# MINI_SAM_2017-01-012.net
KiCad netlist of a schematic drawn in EAGLE
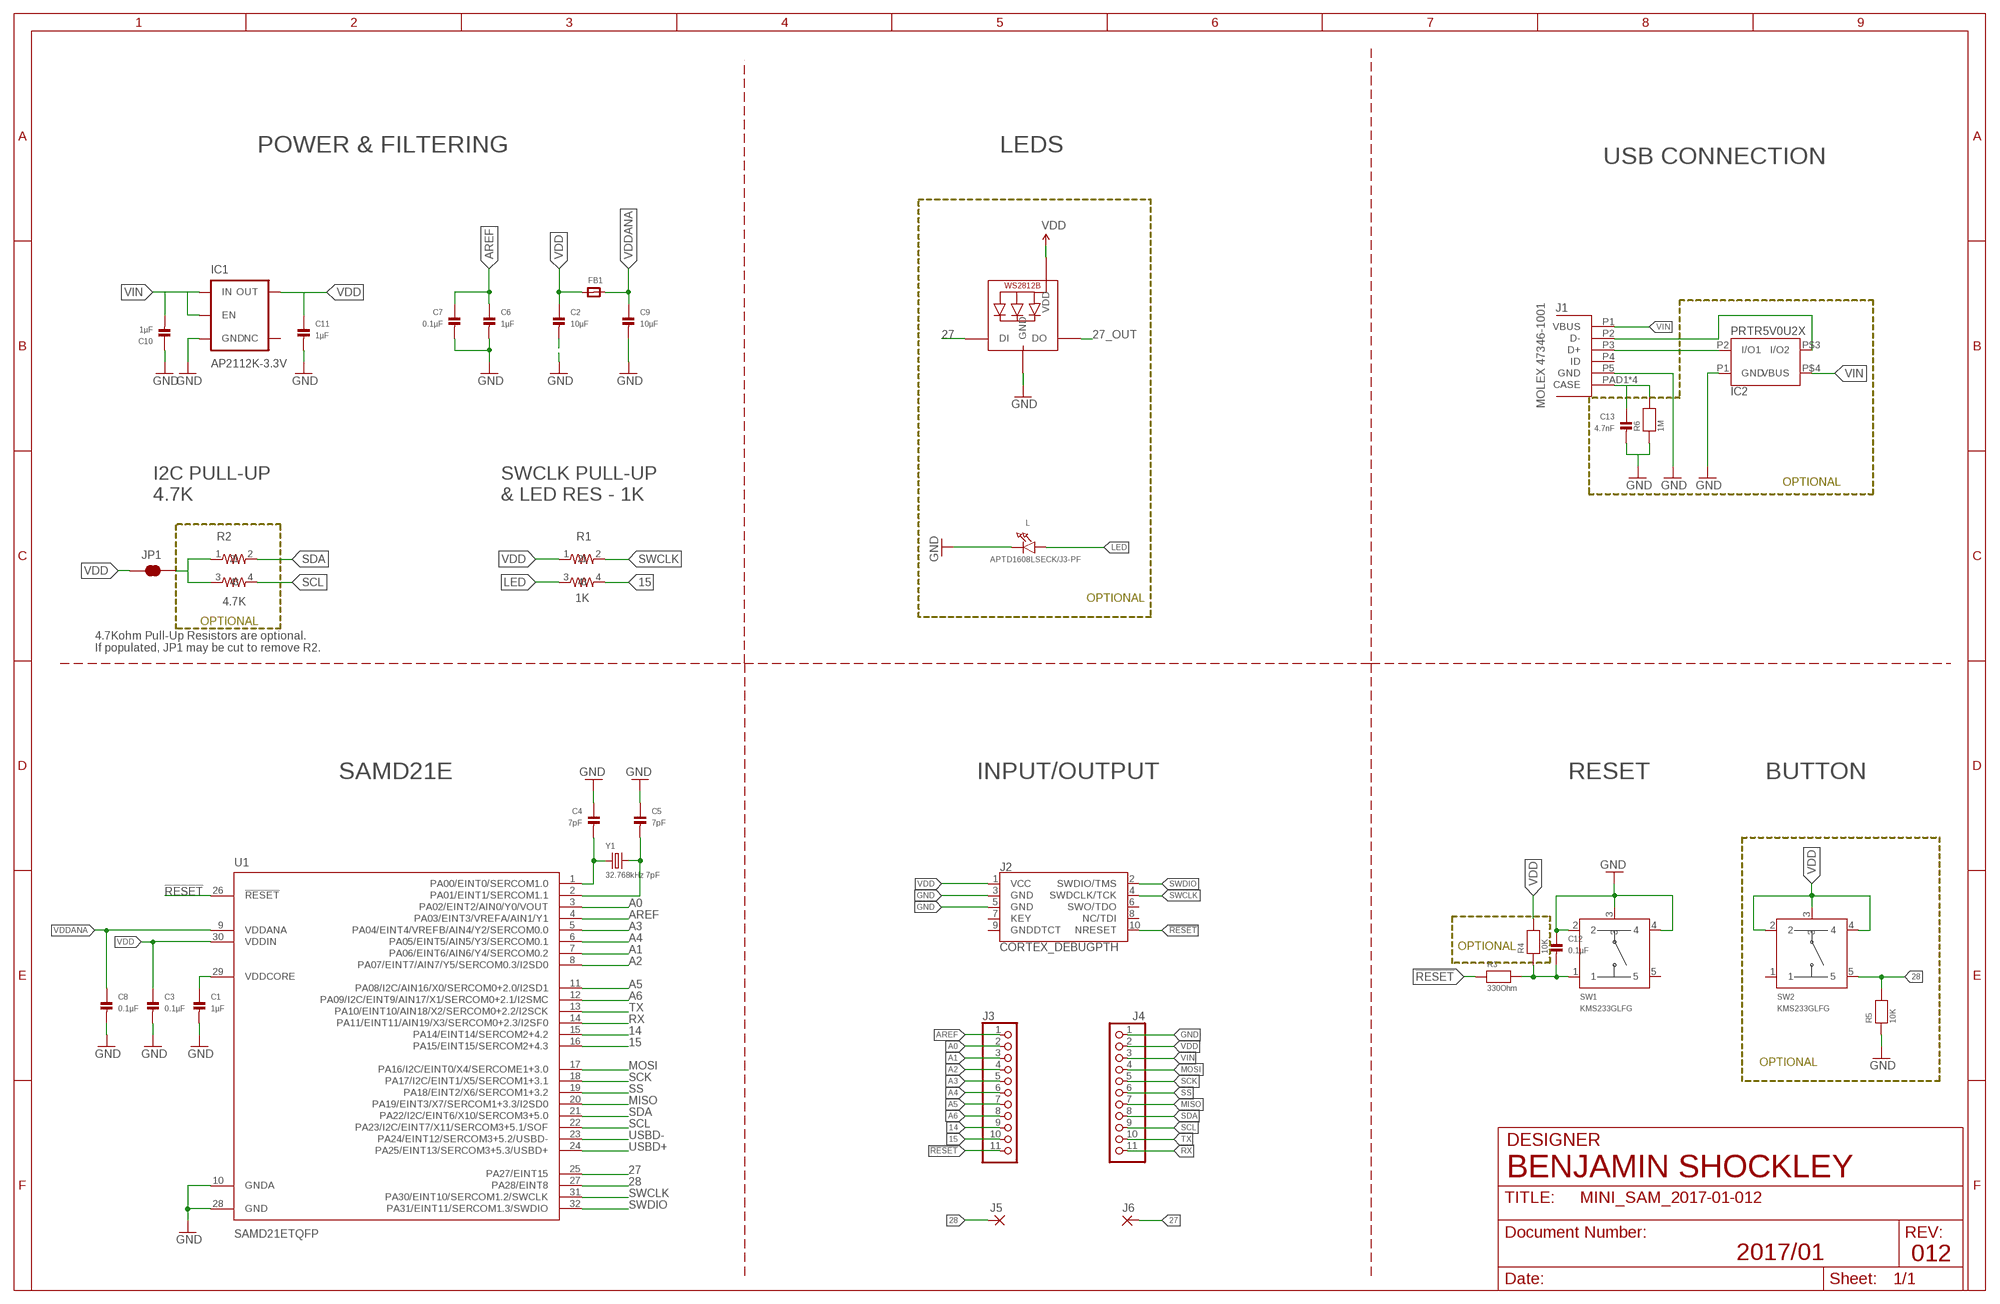
[diagram p0: schematic, sheet 1]

(export (version "E")
  (design (tool "Eeschema 10.0.6"))
  (components
    (comp (ref "C1")
      (value "1µF")
      (footprint "eagle-import:_0805MP")
      (libsource (lib "eagle-import") (part "CAP_CERAMIC_0805MP"))
    )
    (comp (ref "C2")
      (value "10µF")
      (footprint "eagle-import:_0805MP")
      (libsource (lib "eagle-import") (part "CAP_CERAMIC_0805MP"))
    )
    (comp (ref "C3")
      (value "0.1µF")
      (footprint "eagle-import:_0805MP")
      (libsource (lib "eagle-import") (part "CAP_CERAMIC_0805MP"))
    )
    (comp (ref "C4")
      (value "7pF")
      (footprint "eagle-import:_0805MP")
      (libsource (lib "eagle-import") (part "CAP_CERAMIC_0805MP"))
    )
    (comp (ref "C5")
      (value "7pF")
      (footprint "eagle-import:_0805MP")
      (libsource (lib "eagle-import") (part "CAP_CERAMIC_0805MP"))
    )
    (comp (ref "C6")
      (value "1µF")
      (footprint "eagle-import:_0805MP")
      (libsource (lib "eagle-import") (part "CAP_CERAMIC_0805MP"))
    )
    (comp (ref "C7")
      (value "0.1µF")
      (footprint "eagle-import:_0805MP")
      (libsource (lib "eagle-import") (part "CAP_CERAMIC_0805MP"))
    )
    (comp (ref "C8")
      (value "0.1µF")
      (footprint "eagle-import:_0805MP")
      (libsource (lib "eagle-import") (part "CAP_CERAMIC_0805MP"))
    )
    (comp (ref "C9")
      (value "10µF")
      (footprint "eagle-import:_0805MP")
      (libsource (lib "eagle-import") (part "CAP_CERAMIC_0805MP"))
    )
    (comp (ref "C10")
      (value "1µF")
      (footprint "eagle-import:_0805MP")
      (libsource (lib "eagle-import") (part "CAP_CERAMIC_0805MP"))
    )
    (comp (ref "C11")
      (value "1µF")
      (footprint "eagle-import:_0805MP")
      (libsource (lib "eagle-import") (part "CAP_CERAMIC_0805MP"))
    )
    (comp (ref "C12")
      (value "0.1µF")
      (footprint "eagle-import:_0805MP")
      (libsource (lib "eagle-import") (part "CAP_CERAMIC_0805MP"))
    )
    (comp (ref "C13")
      (value "4.7nF")
      (footprint "eagle-import:_0805MP")
      (libsource (lib "eagle-import") (part "CAP_CERAMIC_0805MP"))
    )
    (comp (ref "FB1")
      (value "FERRITE_0805MP")
      (footprint "eagle-import:_0805MP")
      (libsource (lib "eagle-import") (part "FERRITE_0805MP"))
    )
    (comp (ref "IC1")
      (value "AP2112K-3.3V")
      (footprint "eagle-import:SOT23-5")
      (libsource (lib "eagle-import") (part "V_REG_AP2112K-3.3V"))
    )
    (comp (ref "IC2")
      (value "PRTR5V0U2X")
      (footprint "eagle-import:SOT143B_REFLOW")
      (libsource (lib "eagle-import") (part "PRTR5V0U2X"))
    )
    (comp (ref "J1")
      (value "MOLEX_47346-100147346")
      (footprint "eagle-import:MOLEX_47346-1001")
      (libsource (lib "eagle-import") (part "MOLEX_47346-100147346"))
    )
    (comp (ref "J2")
      (value "CORTEX_DEBUGPTH")
      (footprint "eagle-import:2X5-PTH-1.27MM")
      (libsource (lib "eagle-import") (part "CORTEX_DEBUGPTH"))
    )
    (comp (ref "J3")
      (value "PINHD-1X111X11_SMT")
      (footprint "eagle-import:1X11_SMT")
      (libsource (lib "eagle-import") (part "PINHD-1X111X11_SMT"))
    )
    (comp (ref "J4")
      (value "PINHD-1X111X11_SMT")
      (footprint "eagle-import:1X11_SMT")
      (libsource (lib "eagle-import") (part "PINHD-1X111X11_SMT"))
    )
    (comp (ref "J5")
      (value "FR11_PAD2MMX1MM")
      (footprint "eagle-import:SMD2MMX1MM")
      (libsource (lib "eagle-import") (part "FR11_PAD2MMX1MM"))
    )
    (comp (ref "J6")
      (value "FR11_PAD2MMX1MM")
      (footprint "eagle-import:SMD2MMX1MM")
      (libsource (lib "eagle-import") (part "FR11_PAD2MMX1MM"))
    )
    (comp (ref "JP1")
      (value "JUMPER-SMT_2_NC_TRACE_NO-SILK")
      (footprint "eagle-import:SMT-JUMPER_2_NC_TRACE_NO-SILK")
      (libsource (lib "eagle-import") (part "JUMPER-SMT_2_NC_TRACE_NO-SILK"))
    )
    (comp (ref "L")
      (value "APTD1608LSECK/J3-PF")
      (footprint "eagle-import:CHIPLED_0603_NOOUTLINE")
      (libsource (lib "eagle-import") (part "LED0603_NOOUTLINE"))
    )
    (comp (ref "R1")
      (value "1K")
      (footprint "eagle-import:RESISTOR_ARRAY_0606")
      (libsource (lib "eagle-import") (part "RESISTOR_ARRAY_2"))
    )
    (comp (ref "R2")
      (value "4.7K")
      (footprint "eagle-import:RESISTOR_ARRAY_0606")
      (libsource (lib "eagle-import") (part "RESISTOR_ARRAY_2"))
    )
    (comp (ref "R3")
      (value "330Ohm")
      (footprint "eagle-import:_0805MP")
      (libsource (lib "eagle-import") (part "RESISTOR_0805MP"))
    )
    (comp (ref "R4")
      (value "10K")
      (footprint "eagle-import:_0805MP")
      (libsource (lib "eagle-import") (part "RESISTOR_0805MP"))
    )
    (comp (ref "R5")
      (value "10K")
      (footprint "eagle-import:_0805MP")
      (libsource (lib "eagle-import") (part "RESISTOR_0805MP"))
    )
    (comp (ref "R6")
      (value "1M")
      (footprint "eagle-import:_0805MP")
      (libsource (lib "eagle-import") (part "RESISTOR_0805MP"))
    )
    (comp (ref "STATUS")
      (value "WS2812B3535")
      (footprint "eagle-import:LED3535")
      (libsource (lib "eagle-import") (part "WS2812B3535"))
    )
    (comp (ref "SW1")
      (value "KMS233GLFG")
      (footprint "eagle-import:KMS_SWITCH")
      (libsource (lib "eagle-import") (part "KMS_SWITCHKMS"))
    )
    (comp (ref "SW2")
      (value "KMS233GLFG")
      (footprint "eagle-import:KMS_SWITCH")
      (libsource (lib "eagle-import") (part "KMS_SWITCHKMS"))
    )
    (comp (ref "U1")
      (value "SAMD21ETQFP")
      (footprint "eagle-import:TQFP32-08")
      (libsource (lib "eagle-import") (part "SAMD21ETQFP"))
    )
    (comp (ref "Y1")
      (value "32.768kHz 7pF")
      (footprint "eagle-import:_0805MP")
      (libsource (lib "eagle-import") (part "CRYSTAL0805PACKAGE"))
    )
  )
  (nets
    (net (code "1") (name "/27_OUT") (class "Default")
      (node (ref "STATUS") (pin "3") (pinfunction "DO_3") (pintype "output"))
    )
    (net (code "2") (name "/USBD+") (class "Default")
      (node (ref "IC2") (pin "P2") (pinfunction "I/O1_P2") (pintype "bidirectional"))
      (node (ref "J1") (pin "P3") (pinfunction "D+_P3") (pintype "bidirectional"))
      (node (ref "U1") (pin "24") (pinfunction "PA25/EINT13/SERCOM3+5.3/USBD+_24") (pintype "bidirectional"))
    )
    (net (code "3") (name "/USBD-") (class "Default")
      (node (ref "IC2") (pin "P$3") (pinfunction "I/O2_P$3") (pintype "bidirectional"))
      (node (ref "J1") (pin "P2") (pinfunction "D-_P2") (pintype "bidirectional"))
      (node (ref "U1") (pin "23") (pinfunction "PA24/EINT12/SERCOM3+5.2/USBD-_23") (pintype "bidirectional"))
    )
    (net (code "4") (name "/~{RESET}") (class "Default")
      (node (ref "J2") (pin "10") (pinfunction "NRESET_10") (pintype "bidirectional"))
      (node (ref "J3") (pin "11") (pinfunction "11_11") (pintype "passive"))
      (node (ref "R3") (pin "1") (pinfunction "1_1") (pintype "passive"))
      (node (ref "U1") (pin "26") (pinfunction "~{RESET}_26") (pintype "bidirectional"))
    )
    (net (code "5") (name "14") (class "Default")
      (node (ref "J3") (pin "9") (pinfunction "9_9") (pintype "passive"))
      (node (ref "U1") (pin "15") (pinfunction "PA14/EINT14/SERCOM2+4.2_15") (pintype "bidirectional"))
    )
    (net (code "6") (name "15") (class "Default")
      (node (ref "J3") (pin "10") (pinfunction "10_10") (pintype "passive"))
      (node (ref "R1") (pin "4") (pinfunction "4_4") (pintype "passive"))
      (node (ref "U1") (pin "16") (pinfunction "PA15/EINT15/SERCOM2+4.3_16") (pintype "bidirectional"))
    )
    (net (code "7") (name "27") (class "Default")
      (node (ref "J6") (pin "P$1") (pinfunction "P_P$1") (pintype "passive"))
      (node (ref "STATUS") (pin "1") (pinfunction "DI_1") (pintype "input"))
      (node (ref "U1") (pin "25") (pinfunction "PA27/EINT15_25") (pintype "bidirectional"))
    )
    (net (code "8") (name "28") (class "Default")
      (node (ref "J5") (pin "P$1") (pinfunction "P_P$1") (pintype "passive"))
      (node (ref "R5") (pin "2") (pinfunction "2_2") (pintype "passive"))
      (node (ref "SW2") (pin "5") (pinfunction "5_5") (pintype "bidirectional"))
      (node (ref "U1") (pin "27") (pinfunction "PA28/EINT8_27") (pintype "bidirectional"))
    )
    (net (code "9") (name "A0") (class "Default")
      (node (ref "J3") (pin "2") (pinfunction "2_2") (pintype "passive"))
      (node (ref "U1") (pin "3") (pinfunction "PA02/EINT2/AIN0/Y0/VOUT_3") (pintype "bidirectional"))
    )
    (net (code "10") (name "A1") (class "Default")
      (node (ref "J3") (pin "3") (pinfunction "3_3") (pintype "passive"))
      (node (ref "U1") (pin "7") (pinfunction "PA06/EINT6/AIN6/Y4/SERCOM0.2_7") (pintype "bidirectional"))
    )
    (net (code "11") (name "A2") (class "Default")
      (node (ref "J3") (pin "4") (pinfunction "4_4") (pintype "passive"))
      (node (ref "U1") (pin "8") (pinfunction "PA07/EINT7/AIN7/Y5/SERCOM0.3/I2SD0_8") (pintype "bidirectional"))
    )
    (net (code "12") (name "A3") (class "Default")
      (node (ref "J3") (pin "5") (pinfunction "5_5") (pintype "passive"))
      (node (ref "U1") (pin "5") (pinfunction "PA04/EINT4/VREFB/AIN4/Y2/SERCOM0.0_5") (pintype "bidirectional"))
    )
    (net (code "13") (name "A4") (class "Default")
      (node (ref "J3") (pin "6") (pinfunction "6_6") (pintype "passive"))
      (node (ref "U1") (pin "6") (pinfunction "PA05/EINT5/AIN5/Y3/SERCOM0.1_6") (pintype "bidirectional"))
    )
    (net (code "14") (name "A5") (class "Default")
      (node (ref "J3") (pin "7") (pinfunction "7_7") (pintype "passive"))
      (node (ref "U1") (pin "11") (pinfunction "PA08/I2C/AIN16/X0/SERCOM0+2.0/I2SD1_11") (pintype "bidirectional"))
    )
    (net (code "15") (name "A6") (class "Default")
      (node (ref "J3") (pin "8") (pinfunction "8_8") (pintype "passive"))
      (node (ref "U1") (pin "12") (pinfunction "PA09/I2C/EINT9/AIN17/X1/SERCOM0+2.1/I2SMC_12") (pintype "bidirectional"))
    )
    (net (code "16") (name "AREF") (class "Default")
      (node (ref "C6") (pin "1") (pinfunction "P$1_1") (pintype "passive"))
      (node (ref "C7") (pin "1") (pinfunction "P$1_1") (pintype "passive"))
      (node (ref "J3") (pin "1") (pinfunction "1_1") (pintype "passive"))
      (node (ref "U1") (pin "4") (pinfunction "PA03/EINT3/VREFA/AIN1/Y1_4") (pintype "bidirectional"))
    )
    (net (code "17") (name "GND") (class "Default")
      (node (ref "C1") (pin "2") (pinfunction "P$2_2") (pintype "passive"))
      (node (ref "C10") (pin "1") (pinfunction "P$1_1") (pintype "passive"))
      (node (ref "C11") (pin "2") (pinfunction "P$2_2") (pintype "passive"))
      (node (ref "C12") (pin "1") (pinfunction "P$1_1") (pintype "passive"))
      (node (ref "C13") (pin "2") (pinfunction "P$2_2") (pintype "passive"))
      (node (ref "C2") (pin "2") (pinfunction "P$2_2") (pintype "passive"))
      (node (ref "C3") (pin "2") (pinfunction "P$2_2") (pintype "passive"))
      (node (ref "C4") (pin "1") (pinfunction "P$1_1") (pintype "passive"))
      (node (ref "C5") (pin "1") (pinfunction "P$1_1") (pintype "passive"))
      (node (ref "C6") (pin "2") (pinfunction "P$2_2") (pintype "passive"))
      (node (ref "C7") (pin "2") (pinfunction "P$2_2") (pintype "passive"))
      (node (ref "C8") (pin "2") (pinfunction "P$2_2") (pintype "passive"))
      (node (ref "C9") (pin "2") (pinfunction "P$2_2") (pintype "passive"))
      (node (ref "IC1") (pin "2") (pinfunction "GND_2") (pintype "input"))
      (node (ref "IC2") (pin "P1") (pinfunction "GND_P1") (pintype "bidirectional"))
      (node (ref "J1") (pin "P5") (pinfunction "GND_P5") (pintype "power_in"))
      (node (ref "J2") (pin "3") (pinfunction "GND_3") (pintype "bidirectional"))
      (node (ref "J2") (pin "5") (pinfunction "GND_5") (pintype "bidirectional"))
      (node (ref "J4") (pin "1") (pinfunction "1_1") (pintype "passive"))
      (node (ref "L") (pin "C") (pinfunction "C_C") (pintype "passive"))
      (node (ref "R5") (pin "1") (pinfunction "1_1") (pintype "passive"))
      (node (ref "R6") (pin "1") (pinfunction "1_1") (pintype "passive"))
      (node (ref "STATUS") (pin "4") (pinfunction "GND_4") (pintype "power_in"))
      (node (ref "SW1") (pin "2") (pinfunction "2_2") (pintype "bidirectional"))
      (node (ref "SW1") (pin "3") (pinfunction "3_3") (pintype "bidirectional"))
      (node (ref "SW1") (pin "4") (pinfunction "4_4") (pintype "bidirectional"))
      (node (ref "U1") (pin "10") (pinfunction "GNDA_10") (pintype "power_in"))
      (node (ref "U1") (pin "28") (pinfunction "GND_28") (pintype "power_in"))
    )
    (net (code "18") (name "LED") (class "Default")
      (node (ref "L") (pin "A") (pinfunction "A_A") (pintype "passive"))
      (node (ref "R1") (pin "3") (pinfunction "3_3") (pintype "passive"))
    )
    (net (code "19") (name "MISO") (class "Default")
      (node (ref "J4") (pin "7") (pinfunction "7_7") (pintype "passive"))
      (node (ref "U1") (pin "20") (pinfunction "PA19/EINT3/X7/SERCOM1+3.3/I2SD0_20") (pintype "bidirectional"))
    )
    (net (code "20") (name "MOSI") (class "Default")
      (node (ref "J4") (pin "4") (pinfunction "4_4") (pintype "passive"))
      (node (ref "U1") (pin "17") (pinfunction "PA16/I2C/EINT0/X4/SERCOME1+3.0_17") (pintype "bidirectional"))
    )
    (net (code "21") (name "Net-(C1-P$1)") (class "Default")
      (node (ref "C1") (pin "1") (pinfunction "P$1_1") (pintype "passive"))
      (node (ref "U1") (pin "29") (pinfunction "VDDCORE_29") (pintype "power_in"))
    )
    (net (code "22") (name "Net-(C4-P$2)") (class "Default")
      (node (ref "C4") (pin "2") (pinfunction "P$2_2") (pintype "passive"))
      (node (ref "U1") (pin "1") (pinfunction "PA00/EINT0/SERCOM1.0_1") (pintype "bidirectional"))
      (node (ref "Y1") (pin "1") (pinfunction "1_1") (pintype "passive"))
    )
    (net (code "23") (name "Net-(C5-P$2)") (class "Default")
      (node (ref "C5") (pin "2") (pinfunction "P$2_2") (pintype "passive"))
      (node (ref "U1") (pin "2") (pinfunction "PA01/EINT1/SERCOM1.1_2") (pintype "bidirectional"))
      (node (ref "Y1") (pin "2") (pinfunction "2_2") (pintype "passive"))
    )
    (net (code "24") (name "Net-(C12-P$2)") (class "Default")
      (node (ref "C12") (pin "2") (pinfunction "P$2_2") (pintype "passive"))
      (node (ref "R3") (pin "2") (pinfunction "2_2") (pintype "passive"))
      (node (ref "R4") (pin "1") (pinfunction "1_1") (pintype "passive"))
      (node (ref "SW1") (pin "1") (pinfunction "1_1") (pintype "bidirectional"))
    )
    (net (code "25") (name "Net-(C13-P$1)") (class "Default")
      (node (ref "C13") (pin "1") (pinfunction "P$1_1") (pintype "passive"))
      (node (ref "J1") (pin "PAD1") (pinfunction "CASE_PAD1") (pintype "bidirectional"))
      (node (ref "J1") (pin "PAD2") (pinfunction "CASE_PAD2") (pintype "bidirectional"))
      (node (ref "J1") (pin "PAD3") (pinfunction "CASE_PAD3") (pintype "bidirectional"))
      (node (ref "J1") (pin "PAD4") (pinfunction "CASE_PAD4") (pintype "bidirectional"))
      (node (ref "R6") (pin "2") (pinfunction "2_2") (pintype "passive"))
    )
    (net (code "26") (name "Net-(JP1-Pad2)") (class "Default")
      (node (ref "JP1") (pin "2") (pinfunction "2_2") (pintype "passive"))
      (node (ref "R2") (pin "1") (pinfunction "1_1") (pintype "passive"))
      (node (ref "R2") (pin "3") (pinfunction "3_3") (pintype "passive"))
    )
    (net (code "27") (name "RX") (class "Default")
      (node (ref "J4") (pin "11") (pinfunction "11_11") (pintype "passive"))
      (node (ref "U1") (pin "14") (pinfunction "PA11/EINT11/AIN19/X3/SERCOM0+2.3/I2SF0_14") (pintype "bidirectional"))
    )
    (net (code "28") (name "SCK") (class "Default")
      (node (ref "J4") (pin "5") (pinfunction "5_5") (pintype "passive"))
      (node (ref "U1") (pin "18") (pinfunction "PA17/I2C/EINT1/X5/SERCOM1+3.1_18") (pintype "bidirectional"))
    )
    (net (code "29") (name "SCL") (class "Default")
      (node (ref "J4") (pin "9") (pinfunction "9_9") (pintype "passive"))
      (node (ref "R2") (pin "4") (pinfunction "4_4") (pintype "passive"))
      (node (ref "U1") (pin "22") (pinfunction "PA23/I2C/EINT7/X11/SERCOM3+5.1/SOF_22") (pintype "bidirectional"))
    )
    (net (code "30") (name "SDA") (class "Default")
      (node (ref "J4") (pin "8") (pinfunction "8_8") (pintype "passive"))
      (node (ref "R2") (pin "2") (pinfunction "2_2") (pintype "passive"))
      (node (ref "U1") (pin "21") (pinfunction "PA22/I2C/EINT6/X10/SERCOM3+5.0_21") (pintype "bidirectional"))
    )
    (net (code "31") (name "SS") (class "Default")
      (node (ref "J4") (pin "6") (pinfunction "6_6") (pintype "passive"))
      (node (ref "U1") (pin "19") (pinfunction "PA18/EINT2/X6/SERCOM1+3.2_19") (pintype "bidirectional"))
    )
    (net (code "32") (name "SWCLK") (class "Default")
      (node (ref "J2") (pin "4") (pinfunction "SWDCLK/TCK_4") (pintype "bidirectional"))
      (node (ref "R1") (pin "2") (pinfunction "2_2") (pintype "passive"))
      (node (ref "U1") (pin "31") (pinfunction "PA30/EINT10/SERCOM1.2/SWCLK_31") (pintype "bidirectional"))
    )
    (net (code "33") (name "SWDIO") (class "Default")
      (node (ref "J2") (pin "2") (pinfunction "SWDIO/TMS_2") (pintype "bidirectional"))
      (node (ref "U1") (pin "32") (pinfunction "PA31/EINT11/SERCOM1.3/SWDIO_32") (pintype "bidirectional"))
    )
    (net (code "34") (name "TX") (class "Default")
      (node (ref "J4") (pin "10") (pinfunction "10_10") (pintype "passive"))
      (node (ref "U1") (pin "13") (pinfunction "PA10/EINT10/AIN18/X2/SERCOM0+2.2/I2SCK_13") (pintype "bidirectional"))
    )
    (net (code "35") (name "VDD") (class "Default")
      (node (ref "C11") (pin "1") (pinfunction "P$1_1") (pintype "passive"))
      (node (ref "C2") (pin "1") (pinfunction "P$1_1") (pintype "passive"))
      (node (ref "C3") (pin "1") (pinfunction "P$1_1") (pintype "passive"))
      (node (ref "FB1") (pin "1") (pinfunction "P$1_1") (pintype "passive"))
      (node (ref "IC1") (pin "5") (pinfunction "OUT_5") (pintype "passive"))
      (node (ref "J2") (pin "1") (pinfunction "VCC_1") (pintype "bidirectional"))
      (node (ref "J4") (pin "2") (pinfunction "2_2") (pintype "passive"))
      (node (ref "JP1") (pin "1") (pinfunction "1_1") (pintype "passive"))
      (node (ref "R1") (pin "1") (pinfunction "1_1") (pintype "passive"))
      (node (ref "R4") (pin "2") (pinfunction "2_2") (pintype "passive"))
      (node (ref "STATUS") (pin "2") (pinfunction "VDD_2") (pintype "power_in"))
      (node (ref "SW2") (pin "2") (pinfunction "2_2") (pintype "bidirectional"))
      (node (ref "SW2") (pin "3") (pinfunction "3_3") (pintype "bidirectional"))
      (node (ref "SW2") (pin "4") (pinfunction "4_4") (pintype "bidirectional"))
      (node (ref "U1") (pin "30") (pinfunction "VDDIN_30") (pintype "power_in"))
    )
    (net (code "36") (name "VDDANA") (class "Default")
      (node (ref "C8") (pin "1") (pinfunction "P$1_1") (pintype "passive"))
      (node (ref "C9") (pin "1") (pinfunction "P$1_1") (pintype "passive"))
      (node (ref "FB1") (pin "2") (pinfunction "P$2_2") (pintype "passive"))
      (node (ref "U1") (pin "9") (pinfunction "VDDANA_9") (pintype "power_in"))
    )
    (net (code "37") (name "VIN") (class "Default")
      (node (ref "C10") (pin "2") (pinfunction "P$2_2") (pintype "passive"))
      (node (ref "IC1") (pin "1") (pinfunction "IN_1") (pintype "input"))
      (node (ref "IC1") (pin "3") (pinfunction "EN_3") (pintype "input"))
      (node (ref "IC2") (pin "P$4") (pinfunction "VBUS_P$4") (pintype "bidirectional"))
      (node (ref "J1") (pin "P1") (pinfunction "VBUS_P1") (pintype "power_in"))
      (node (ref "J4") (pin "3") (pinfunction "3_3") (pintype "passive"))
    )
    (net (code "38") (name "unconnected-(IC1-NC-Pad4)") (class "Default")
      (node (ref "IC1") (pin "4") (pinfunction "NC_4") (pintype "input"))
    )
    (net (code "39") (name "unconnected-(J1-ID-PadP4)") (class "Default")
      (node (ref "J1") (pin "P4") (pinfunction "ID_P4") (pintype "bidirectional"))
    )
    (net (code "40") (name "unconnected-(J2-GNDDTCT-Pad9)") (class "Default")
      (node (ref "J2") (pin "9") (pinfunction "GNDDTCT_9") (pintype "bidirectional"))
    )
    (net (code "41") (name "unconnected-(J2-KEY-Pad7)") (class "Default")
      (node (ref "J2") (pin "7") (pinfunction "KEY_7") (pintype "bidirectional"))
    )
    (net (code "42") (name "unconnected-(J2-NC{slash}TDI-Pad8)") (class "Default")
      (node (ref "J2") (pin "8") (pinfunction "NC/TDI_8") (pintype "bidirectional"))
    )
    (net (code "43") (name "unconnected-(J2-SWO{slash}TDO-Pad6)") (class "Default")
      (node (ref "J2") (pin "6") (pinfunction "SWO/TDO_6") (pintype "bidirectional"))
    )
    (net (code "44") (name "unconnected-(SW1-Pad5)") (class "Default")
      (node (ref "SW1") (pin "5") (pinfunction "5_5") (pintype "bidirectional"))
    )
    (net (code "45") (name "unconnected-(SW2-Pad1)") (class "Default")
      (node (ref "SW2") (pin "1") (pinfunction "1_1") (pintype "bidirectional"))
    )
  )
)
